# secondboard2.net
KiCad netlist of a schematic drawn in EAGLE
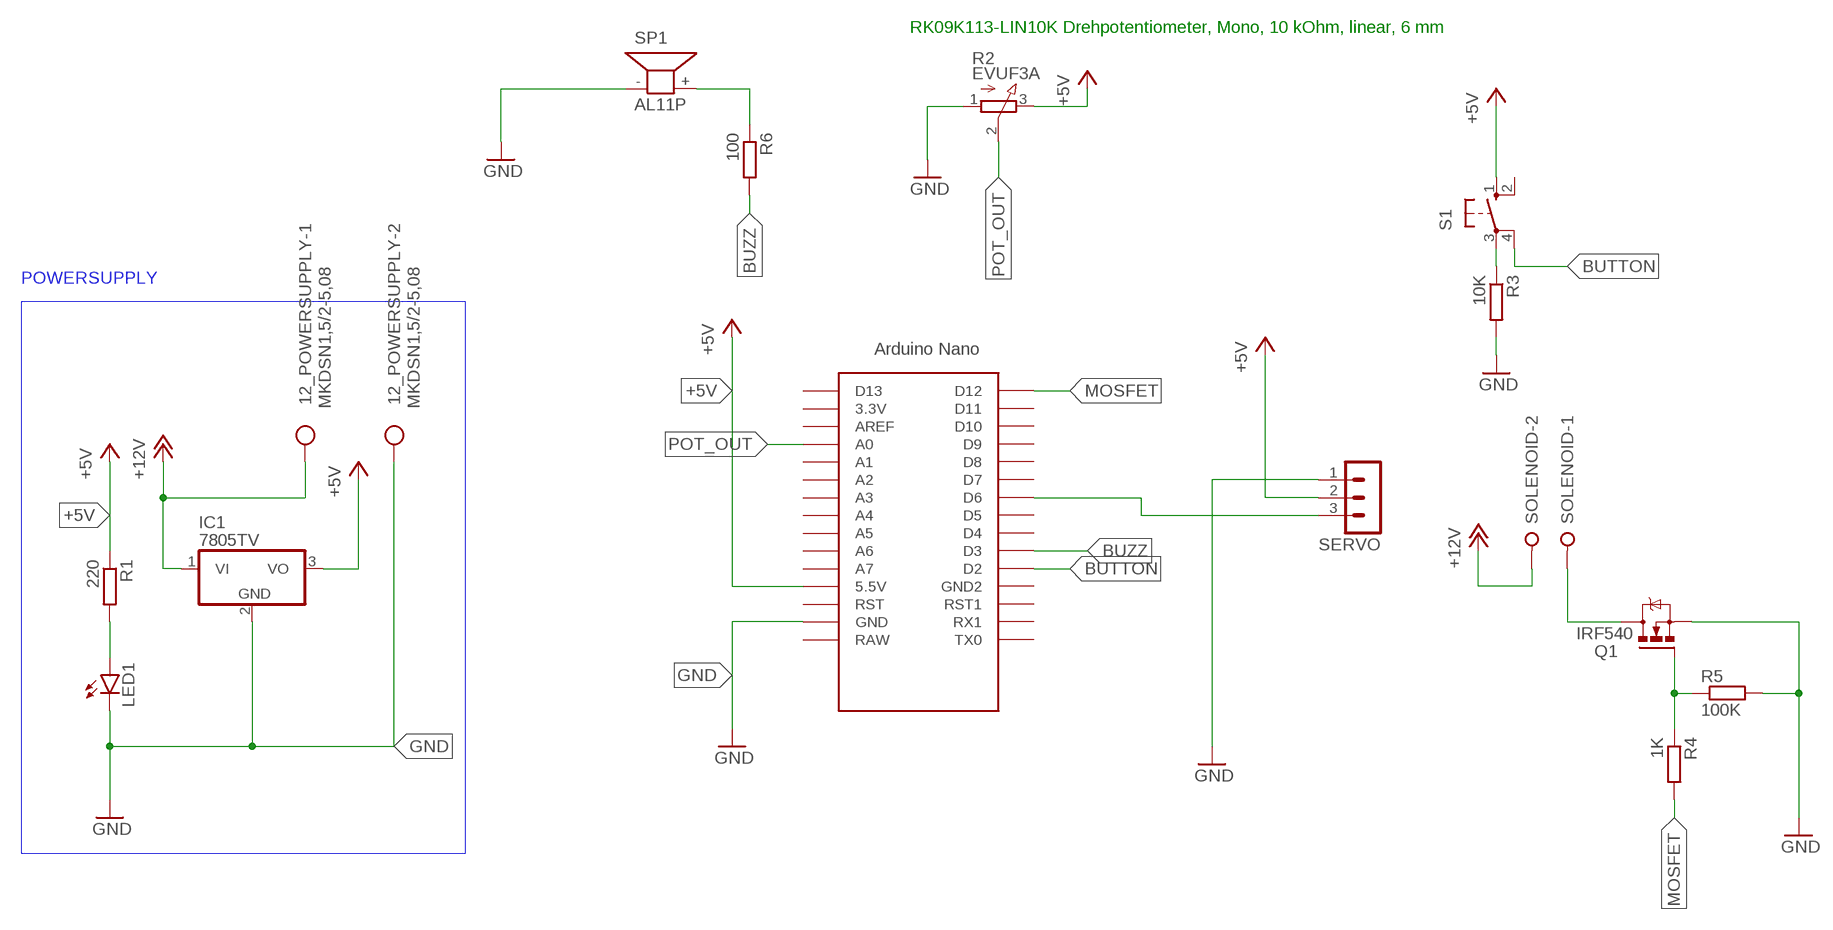
[diagram p0: schematic, sheet 1]

(export (version "E")
  (design (tool "Eeschema 10.0.6"))
  (components
    (comp (ref "12_POWERSUPPLY")
      (value "MKDSN1,5/2-5,08")
      (footprint "eagle-import:MKDSN1,5_2-5,08")
      (libsource (lib "eagle-import") (part "MKDSN1,5/2-5,08"))
    )
    (comp (ref "IC1")
      (value "7805TV")
      (footprint "eagle-import:TO220V")
      (libsource (lib "eagle-import") (part "78TV05"))
    )
    (comp (ref "LED1")
      (value "LED3MM")
      (footprint "eagle-import:LED3MM")
      (libsource (lib "eagle-import") (part "LED3MM"))
    )
    (comp (ref "Q1")
      (value "IRF540")
      (footprint "eagle-import:TO220BV")
      (libsource (lib "eagle-import") (part "IRF540"))
    )
    (comp (ref "R1")
      (value "220")
      (footprint "eagle-import:R0805")
      (libsource (lib "eagle-import") (part "R-EU_R0805"))
    )
    (comp (ref "R2")
      (value "EVUF3A")
      (footprint "eagle-import:EVUF")
      (libsource (lib "eagle-import") (part "EVUAF3"))
    )
    (comp (ref "R3")
      (value "10K")
      (footprint "eagle-import:R0805")
      (libsource (lib "eagle-import") (part "R-EU_R0805"))
    )
    (comp (ref "R4")
      (value "1K")
      (footprint "eagle-import:R0805")
      (libsource (lib "eagle-import") (part "R-EU_R0805"))
    )
    (comp (ref "R5")
      (value "100K")
      (footprint "eagle-import:R0805")
      (libsource (lib "eagle-import") (part "R-EU_R0805"))
    )
    (comp (ref "R6")
      (value "100")
      (footprint "eagle-import:R0805")
      (libsource (lib "eagle-import") (part "R-EU_R0805"))
    )
    (comp (ref "S1")
      (value "10-XX")
      (footprint "eagle-import:B3F-10XX")
      (fields (field (name "MPN") "B3F-1000"))
      (libsource (lib "eagle-import") (part "10-XX"))
    )
    (comp (ref "SERVO")
      (value "MA03-1")
      (footprint "eagle-import:MA03-1")
      (libsource (lib "eagle-import") (part "MA03-1"))
    )
    (comp (ref "SOLENOID")
      (value "W237-02P")
      (footprint "eagle-import:W237-132")
      (libsource (lib "eagle-import") (part "W237-02P"))
    )
    (comp (ref "SP1")
      (value "AL11P")
      (footprint "eagle-import:AL11P")
      (libsource (lib "eagle-import") (part "AL11P"))
    )
    (comp (ref "U$1")
      (value "NANO")
      (footprint "eagle-import:NANO")
      (libsource (lib "eagle-import") (part "NANO"))
    )
  )
  (nets
    (net (code "1") (name "+5V") (class "Default")
      (node (ref "IC1") (pin "3") (pinfunction "VO_3") (pintype "passive"))
      (node (ref "R1") (pin "1") (pinfunction "1_1") (pintype "passive"))
      (node (ref "R2") (pin "3") (pinfunction "E_3") (pintype "passive"))
      (node (ref "S1") (pin "1") (pinfunction "S_1") (pintype "passive"))
      (node (ref "SERVO") (pin "2") (pinfunction "2_2") (pintype "passive"))
      (node (ref "U$1") (pin "5V") (pinfunction "5.5V_5V") (pintype "bidirectional"))
    )
    (net (code "2") (name "+12V") (class "Default")
      (node (ref "12_POWERSUPPLY") (pin "1") (pinfunction "KL_1") (pintype "passive"))
      (node (ref "IC1") (pin "1") (pinfunction "VI_1") (pintype "input"))
      (node (ref "SOLENOID") (pin "2") (pinfunction "KL_2") (pintype "passive"))
    )
    (net (code "3") (name "BUTTON") (class "Default")
      (node (ref "S1") (pin "4") (pinfunction "P1_4") (pintype "passive"))
      (node (ref "U$1") (pin "D2") (pinfunction "D2_D2") (pintype "bidirectional"))
    )
    (net (code "4") (name "BUZZ") (class "Default")
      (node (ref "R6") (pin "2") (pinfunction "2_2") (pintype "passive"))
      (node (ref "U$1") (pin "D3") (pinfunction "D3_D3") (pintype "bidirectional"))
    )
    (net (code "5") (name "GND") (class "Default")
      (node (ref "12_POWERSUPPLY") (pin "2") (pinfunction "KL_2") (pintype "passive"))
      (node (ref "IC1") (pin "2") (pinfunction "GND_2") (pintype "passive"))
      (node (ref "LED1") (pin "K") (pinfunction "C_K") (pintype "passive"))
      (node (ref "Q1") (pin "S") (pinfunction "S_S") (pintype "passive"))
      (node (ref "R2") (pin "1") (pinfunction "A_1") (pintype "passive"))
      (node (ref "R3") (pin "2") (pinfunction "2_2") (pintype "passive"))
      (node (ref "R5") (pin "2") (pinfunction "2_2") (pintype "passive"))
      (node (ref "SERVO") (pin "1") (pinfunction "1_1") (pintype "passive"))
      (node (ref "SP1") (pin "-") (pinfunction "1_-") (pintype "passive"))
      (node (ref "U$1") (pin "GND") (pinfunction "GND_GND") (pintype "bidirectional"))
    )
    (net (code "6") (name "MOSFET") (class "Default")
      (node (ref "R4") (pin "2") (pinfunction "2_2") (pintype "passive"))
      (node (ref "U$1") (pin "D12") (pinfunction "D12_D12") (pintype "bidirectional"))
    )
    (net (code "7") (name "Net-(LED1-PadA)") (class "Default")
      (node (ref "LED1") (pin "A") (pinfunction "A_A") (pintype "passive"))
      (node (ref "R1") (pin "2") (pinfunction "2_2") (pintype "passive"))
    )
    (net (code "8") (name "Net-(Q1-PadG)") (class "Default")
      (node (ref "Q1") (pin "G") (pinfunction "G_G") (pintype "passive"))
      (node (ref "R4") (pin "1") (pinfunction "1_1") (pintype "passive"))
      (node (ref "R5") (pin "1") (pinfunction "1_1") (pintype "passive"))
    )
    (net (code "9") (name "Net-(S1-P)") (class "Default")
      (node (ref "R3") (pin "1") (pinfunction "1_1") (pintype "passive"))
      (node (ref "S1") (pin "3") (pinfunction "P_3") (pintype "passive"))
    )
    (net (code "10") (name "Net-(SERVO-Pad3)") (class "Default")
      (node (ref "SERVO") (pin "3") (pinfunction "3_3") (pintype "passive"))
      (node (ref "U$1") (pin "D6") (pinfunction "D6_D6") (pintype "bidirectional"))
    )
    (net (code "11") (name "Net-(SOLENOIDA-KL)") (class "Default")
      (node (ref "Q1") (pin "D") (pinfunction "D_D") (pintype "passive"))
      (node (ref "SOLENOID") (pin "1") (pinfunction "KL_1") (pintype "passive"))
    )
    (net (code "12") (name "Net-(SP1-2)") (class "Default")
      (node (ref "R6") (pin "1") (pinfunction "1_1") (pintype "passive"))
      (node (ref "SP1") (pin "+") (pinfunction "2_+") (pintype "passive"))
    )
    (net (code "13") (name "POT_OUT") (class "Default")
      (node (ref "R2") (pin "2") (pinfunction "S_2") (pintype "passive"))
      (node (ref "U$1") (pin "A0") (pinfunction "A0_A0") (pintype "bidirectional"))
    )
    (net (code "14") (name "unconnected-(S1-S1-Pad2)") (class "Default")
      (node (ref "S1") (pin "2") (pinfunction "S1_2") (pintype "passive"))
    )
    (net (code "15") (name "unconnected-(U$1-GND2-PadGND1)") (class "Default")
      (node (ref "U$1") (pin "GND1") (pinfunction "GND2_GND1") (pintype "bidirectional"))
    )
    (net (code "16") (name "unconnected-(U$1-Pad3.3V)") (class "Default")
      (node (ref "U$1") (pin "3.3V") (pinfunction "3.3V_3.3V") (pintype "bidirectional"))
    )
    (net (code "17") (name "unconnected-(U$1-PadA1)") (class "Default")
      (node (ref "U$1") (pin "A1") (pinfunction "A1_A1") (pintype "bidirectional"))
    )
    (net (code "18") (name "unconnected-(U$1-PadA2)") (class "Default")
      (node (ref "U$1") (pin "A2") (pinfunction "A2_A2") (pintype "bidirectional"))
    )
    (net (code "19") (name "unconnected-(U$1-PadA3)") (class "Default")
      (node (ref "U$1") (pin "A3") (pinfunction "A3_A3") (pintype "bidirectional"))
    )
    (net (code "20") (name "unconnected-(U$1-PadA4)") (class "Default")
      (node (ref "U$1") (pin "A4") (pinfunction "A4_A4") (pintype "bidirectional"))
    )
    (net (code "21") (name "unconnected-(U$1-PadA5)") (class "Default")
      (node (ref "U$1") (pin "A5") (pinfunction "A5_A5") (pintype "bidirectional"))
    )
    (net (code "22") (name "unconnected-(U$1-PadA6)") (class "Default")
      (node (ref "U$1") (pin "A6") (pinfunction "A6_A6") (pintype "bidirectional"))
    )
    (net (code "23") (name "unconnected-(U$1-PadA7)") (class "Default")
      (node (ref "U$1") (pin "A7") (pinfunction "A7_A7") (pintype "bidirectional"))
    )
    (net (code "24") (name "unconnected-(U$1-PadAREF)") (class "Default")
      (node (ref "U$1") (pin "AREF") (pinfunction "AREF_AREF") (pintype "bidirectional"))
    )
    (net (code "25") (name "unconnected-(U$1-PadD4)") (class "Default")
      (node (ref "U$1") (pin "D4") (pinfunction "D4_D4") (pintype "bidirectional"))
    )
    (net (code "26") (name "unconnected-(U$1-PadD5)") (class "Default")
      (node (ref "U$1") (pin "D5") (pinfunction "D5_D5") (pintype "bidirectional"))
    )
    (net (code "27") (name "unconnected-(U$1-PadD7)") (class "Default")
      (node (ref "U$1") (pin "D7") (pinfunction "D7_D7") (pintype "bidirectional"))
    )
    (net (code "28") (name "unconnected-(U$1-PadD8)") (class "Default")
      (node (ref "U$1") (pin "D8") (pinfunction "D8_D8") (pintype "bidirectional"))
    )
    (net (code "29") (name "unconnected-(U$1-PadD9)") (class "Default")
      (node (ref "U$1") (pin "D9") (pinfunction "D9_D9") (pintype "bidirectional"))
    )
    (net (code "30") (name "unconnected-(U$1-PadD10)") (class "Default")
      (node (ref "U$1") (pin "D10") (pinfunction "D10_D10") (pintype "bidirectional"))
    )
    (net (code "31") (name "unconnected-(U$1-PadD11)") (class "Default")
      (node (ref "U$1") (pin "D11") (pinfunction "D11_D11") (pintype "bidirectional"))
    )
    (net (code "32") (name "unconnected-(U$1-PadD13)") (class "Default")
      (node (ref "U$1") (pin "D13") (pinfunction "D13_D13") (pintype "bidirectional"))
    )
    (net (code "33") (name "unconnected-(U$1-PadICSP1)") (class "Default")
      (node (ref "U$1") (pin "ICSP1") (pinfunction "ICSP1_ICSP1") (pintype "bidirectional"))
    )
    (net (code "34") (name "unconnected-(U$1-PadICSP2)") (class "Default")
      (node (ref "U$1") (pin "ICSP2") (pinfunction "ICSP2_ICSP2") (pintype "bidirectional"))
    )
    (net (code "35") (name "unconnected-(U$1-PadICSP3)") (class "Default")
      (node (ref "U$1") (pin "ICSP3") (pinfunction "ICSP3_ICSP3") (pintype "bidirectional"))
    )
    (net (code "36") (name "unconnected-(U$1-PadICSP4)") (class "Default")
      (node (ref "U$1") (pin "ICSP4") (pinfunction "ICSP4_ICSP4") (pintype "bidirectional"))
    )
    (net (code "37") (name "unconnected-(U$1-PadICSP5)") (class "Default")
      (node (ref "U$1") (pin "ICSP5") (pinfunction "ICSP5_ICSP5") (pintype "bidirectional"))
    )
    (net (code "38") (name "unconnected-(U$1-PadICSP6)") (class "Default")
      (node (ref "U$1") (pin "ICSP6") (pinfunction "ICSP6_ICSP6") (pintype "bidirectional"))
    )
    (net (code "39") (name "unconnected-(U$1-PadRAW)") (class "Default")
      (node (ref "U$1") (pin "RAW") (pinfunction "RAW_RAW") (pintype "bidirectional"))
    )
    (net (code "40") (name "unconnected-(U$1-PadRST)") (class "Default")
      (node (ref "U$1") (pin "RST") (pinfunction "RST_RST") (pintype "bidirectional"))
    )
    (net (code "41") (name "unconnected-(U$1-PadRST1)") (class "Default")
      (node (ref "U$1") (pin "RST1") (pinfunction "RST1_RST1") (pintype "bidirectional"))
    )
    (net (code "42") (name "unconnected-(U$1-PadRX1)") (class "Default")
      (node (ref "U$1") (pin "RX1") (pinfunction "RX1_RX1") (pintype "bidirectional"))
    )
    (net (code "43") (name "unconnected-(U$1-PadTX0)") (class "Default")
      (node (ref "U$1") (pin "TX0") (pinfunction "TX0_TX0") (pintype "bidirectional"))
    )
  )
)
